# aw_301_runner.net
KiCad netlist of a schematic drawn in EAGLE
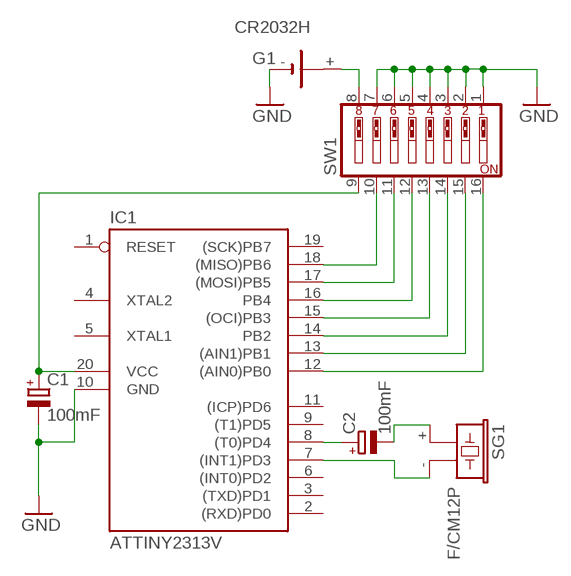
[diagram p0: schematic, sheet 1]

(export (version "E")
  (design (tool "Eeschema 10.0.6"))
  (components
    (comp (ref "C1")
      (value "100mF")
      (footprint "eagle-import:E2,5-6")
      (libsource (lib "eagle-import") (part "CPOL-EUE2.5-6"))
    )
    (comp (ref "C2")
      (value "100mF")
      (footprint "eagle-import:E2,5-6")
      (libsource (lib "eagle-import") (part "CPOL-EUE2.5-6"))
    )
    (comp (ref "G1")
      (value "CR2032H")
      (footprint "eagle-import:CR2032H")
      (libsource (lib "eagle-import") (part "CR2032H"))
    )
    (comp (ref "IC1")
      (value "ATTINY2313V")
      (footprint "eagle-import:DIL20")
      (libsource (lib "eagle-import") (part "AT90S2313P"))
    )
    (comp (ref "SG1")
      (value "F/CM12P")
      (footprint "eagle-import:F_CM12P")
      (libsource (lib "eagle-import") (part "F/CM12P"))
    )
    (comp (ref "SW1")
      (value "SW_DIP-8")
      (footprint "eagle-import:EDG-08")
      (libsource (lib "eagle-import") (part "SW_DIP-8"))
    )
  )
  (nets
    (net (code "1") (name "GND") (class "Default")
      (node (ref "C1") (pin "-") (pinfunction "-_-") (pintype "passive"))
      (node (ref "G1") (pin "-") (pinfunction "-_-") (pintype "passive"))
      (node (ref "IC1") (pin "10") (pinfunction "GND_10") (pintype "power_in"))
      (node (ref "SW1") (pin "1") (pinfunction "1_1") (pintype "passive"))
      (node (ref "SW1") (pin "2") (pinfunction "2_2") (pintype "passive"))
      (node (ref "SW1") (pin "3") (pinfunction "3_3") (pintype "passive"))
      (node (ref "SW1") (pin "4") (pinfunction "4_4") (pintype "passive"))
      (node (ref "SW1") (pin "5") (pinfunction "5_5") (pintype "passive"))
      (node (ref "SW1") (pin "6") (pinfunction "6_6") (pintype "passive"))
      (node (ref "SW1") (pin "7") (pinfunction "7_7") (pintype "passive"))
    )
    (net (code "2") (name "Net-(G1-Pad+)") (class "Default")
      (node (ref "G1") (pin "+") (pinfunction "+_+") (pintype "passive"))
      (node (ref "SW1") (pin "8") (pinfunction "8_8") (pintype "passive"))
    )
    (net (code "3") (name "Net-(IC1-(AIN0)PB0)") (class "Default")
      (node (ref "IC1") (pin "12") (pinfunction "(AIN0)PB0_12") (pintype "bidirectional"))
      (node (ref "SW1") (pin "16") (pinfunction "16_16") (pintype "passive"))
    )
    (net (code "4") (name "Net-(IC1-(AIN1)PB1)") (class "Default")
      (node (ref "IC1") (pin "13") (pinfunction "(AIN1)PB1_13") (pintype "bidirectional"))
      (node (ref "SW1") (pin "15") (pinfunction "15_15") (pintype "passive"))
    )
    (net (code "5") (name "Net-(IC1-(INT1)PD3)") (class "Default")
      (node (ref "IC1") (pin "7") (pinfunction "(INT1)PD3_7") (pintype "bidirectional"))
      (node (ref "SG1") (pin "-") (pinfunction "2_-") (pintype "passive"))
    )
    (net (code "6") (name "Net-(IC1-(MISO)PB6)") (class "Default")
      (node (ref "IC1") (pin "18") (pinfunction "(MISO)PB6_18") (pintype "bidirectional"))
      (node (ref "SW1") (pin "10") (pinfunction "10_10") (pintype "passive"))
    )
    (net (code "7") (name "Net-(IC1-(MOSI)PB5)") (class "Default")
      (node (ref "IC1") (pin "17") (pinfunction "(MOSI)PB5_17") (pintype "bidirectional"))
      (node (ref "SW1") (pin "11") (pinfunction "11_11") (pintype "passive"))
    )
    (net (code "8") (name "Net-(IC1-(OCI)PB3)") (class "Default")
      (node (ref "IC1") (pin "15") (pinfunction "(OCI)PB3_15") (pintype "bidirectional"))
      (node (ref "SW1") (pin "13") (pinfunction "13_13") (pintype "passive"))
    )
    (net (code "9") (name "Net-(IC1-(T0)PD4)") (class "Default")
      (node (ref "C2") (pin "+") (pinfunction "+_+") (pintype "passive"))
      (node (ref "IC1") (pin "8") (pinfunction "(T0)PD4_8") (pintype "bidirectional"))
    )
    (net (code "10") (name "Net-(IC1-PB2)") (class "Default")
      (node (ref "IC1") (pin "14") (pinfunction "PB2_14") (pintype "bidirectional"))
      (node (ref "SW1") (pin "14") (pinfunction "14_14") (pintype "passive"))
    )
    (net (code "11") (name "Net-(IC1-PB4)") (class "Default")
      (node (ref "IC1") (pin "16") (pinfunction "PB4_16") (pintype "bidirectional"))
      (node (ref "SW1") (pin "12") (pinfunction "12_12") (pintype "passive"))
    )
    (net (code "12") (name "Net-(IC1-VCC)") (class "Default")
      (node (ref "C1") (pin "+") (pinfunction "+_+") (pintype "passive"))
      (node (ref "IC1") (pin "20") (pinfunction "VCC_20") (pintype "power_in"))
      (node (ref "SW1") (pin "9") (pinfunction "9_9") (pintype "passive"))
    )
    (net (code "13") (name "Net-(SG1-1)") (class "Default")
      (node (ref "C2") (pin "-") (pinfunction "-_-") (pintype "passive"))
      (node (ref "SG1") (pin "+") (pinfunction "1_+") (pintype "passive"))
    )
    (net (code "14") (name "unconnected-(G1-+-Pad+@1)") (class "Default")
      (node (ref "G1") (pin "+@1") (pinfunction "+_+@1") (pintype "passive"))
    )
    (net (code "15") (name "unconnected-(IC1-(ICP)PD6-Pad11)") (class "Default")
      (node (ref "IC1") (pin "11") (pinfunction "(ICP)PD6_11") (pintype "bidirectional"))
    )
    (net (code "16") (name "unconnected-(IC1-(INT0)PD2-Pad6)") (class "Default")
      (node (ref "IC1") (pin "6") (pinfunction "(INT0)PD2_6") (pintype "bidirectional"))
    )
    (net (code "17") (name "unconnected-(IC1-(RXD)PD0-Pad2)") (class "Default")
      (node (ref "IC1") (pin "2") (pinfunction "(RXD)PD0_2") (pintype "bidirectional"))
    )
    (net (code "18") (name "unconnected-(IC1-(SCK)PB7-Pad19)") (class "Default")
      (node (ref "IC1") (pin "19") (pinfunction "(SCK)PB7_19") (pintype "bidirectional"))
    )
    (net (code "19") (name "unconnected-(IC1-(T1)PD5-Pad9)") (class "Default")
      (node (ref "IC1") (pin "9") (pinfunction "(T1)PD5_9") (pintype "bidirectional"))
    )
    (net (code "20") (name "unconnected-(IC1-(TXD)PD1-Pad3)") (class "Default")
      (node (ref "IC1") (pin "3") (pinfunction "(TXD)PD1_3") (pintype "bidirectional"))
    )
    (net (code "21") (name "unconnected-(IC1-RESET-Pad1)") (class "Default")
      (node (ref "IC1") (pin "1") (pinfunction "RESET_1") (pintype "bidirectional"))
    )
    (net (code "22") (name "unconnected-(IC1-XTAL1-Pad5)") (class "Default")
      (node (ref "IC1") (pin "5") (pinfunction "XTAL1_5") (pintype "bidirectional"))
    )
    (net (code "23") (name "unconnected-(IC1-XTAL2-Pad4)") (class "Default")
      (node (ref "IC1") (pin "4") (pinfunction "XTAL2_4") (pintype "bidirectional"))
    )
  )
)
